# main-unit-psu.net
KiCad netlist of a schematic drawn in EAGLE
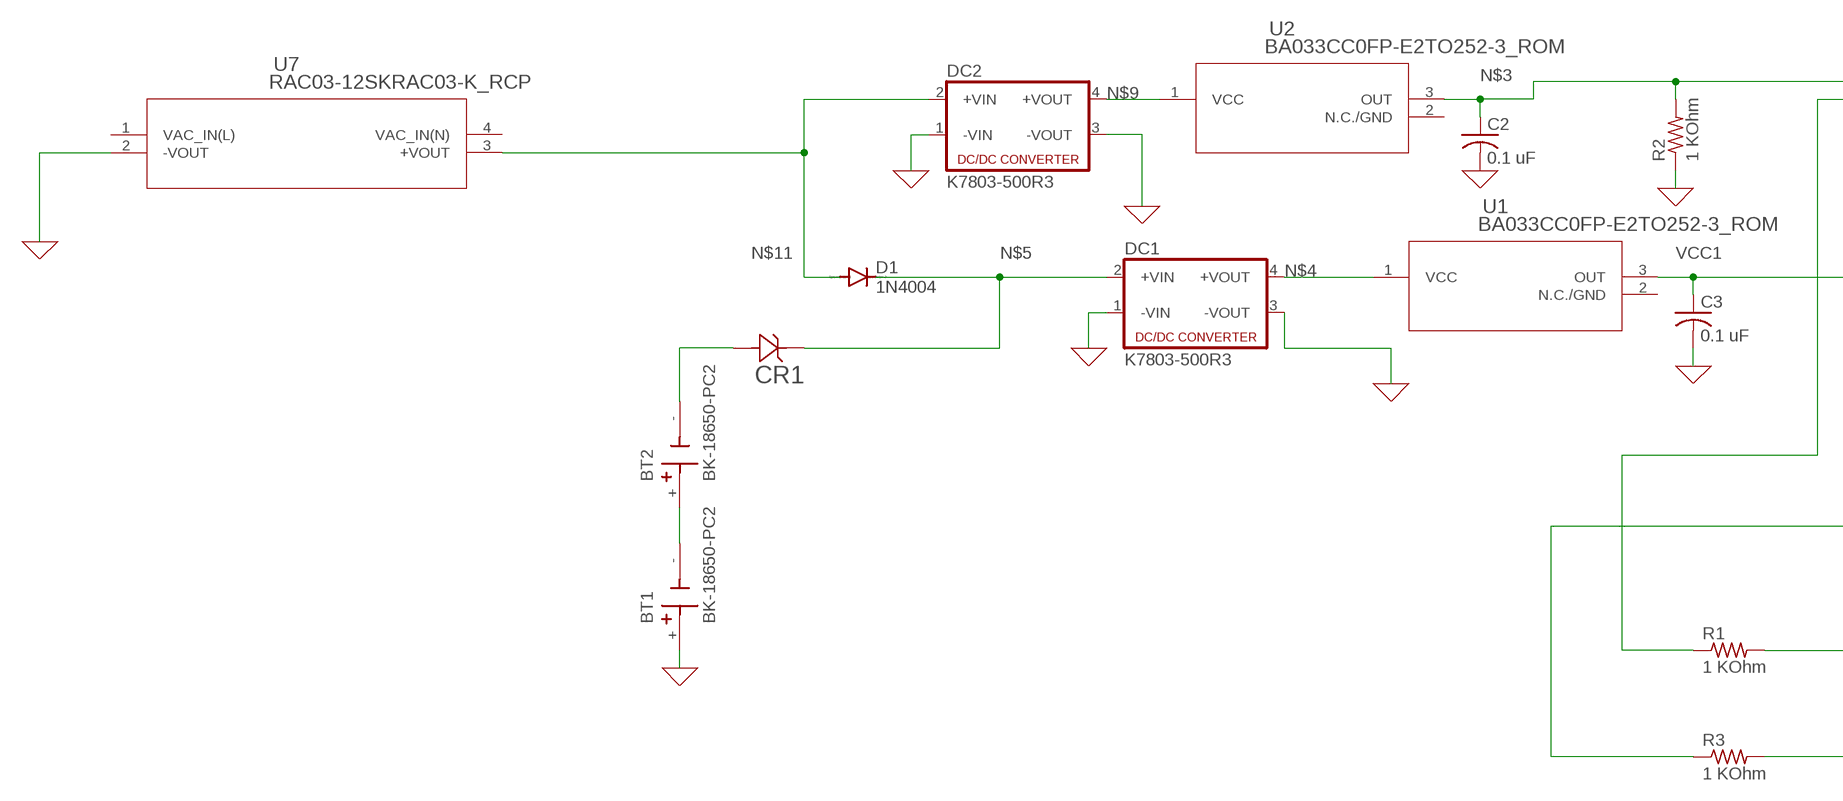
[diagram p0: schematic, sheet 1, part 1 of 2]
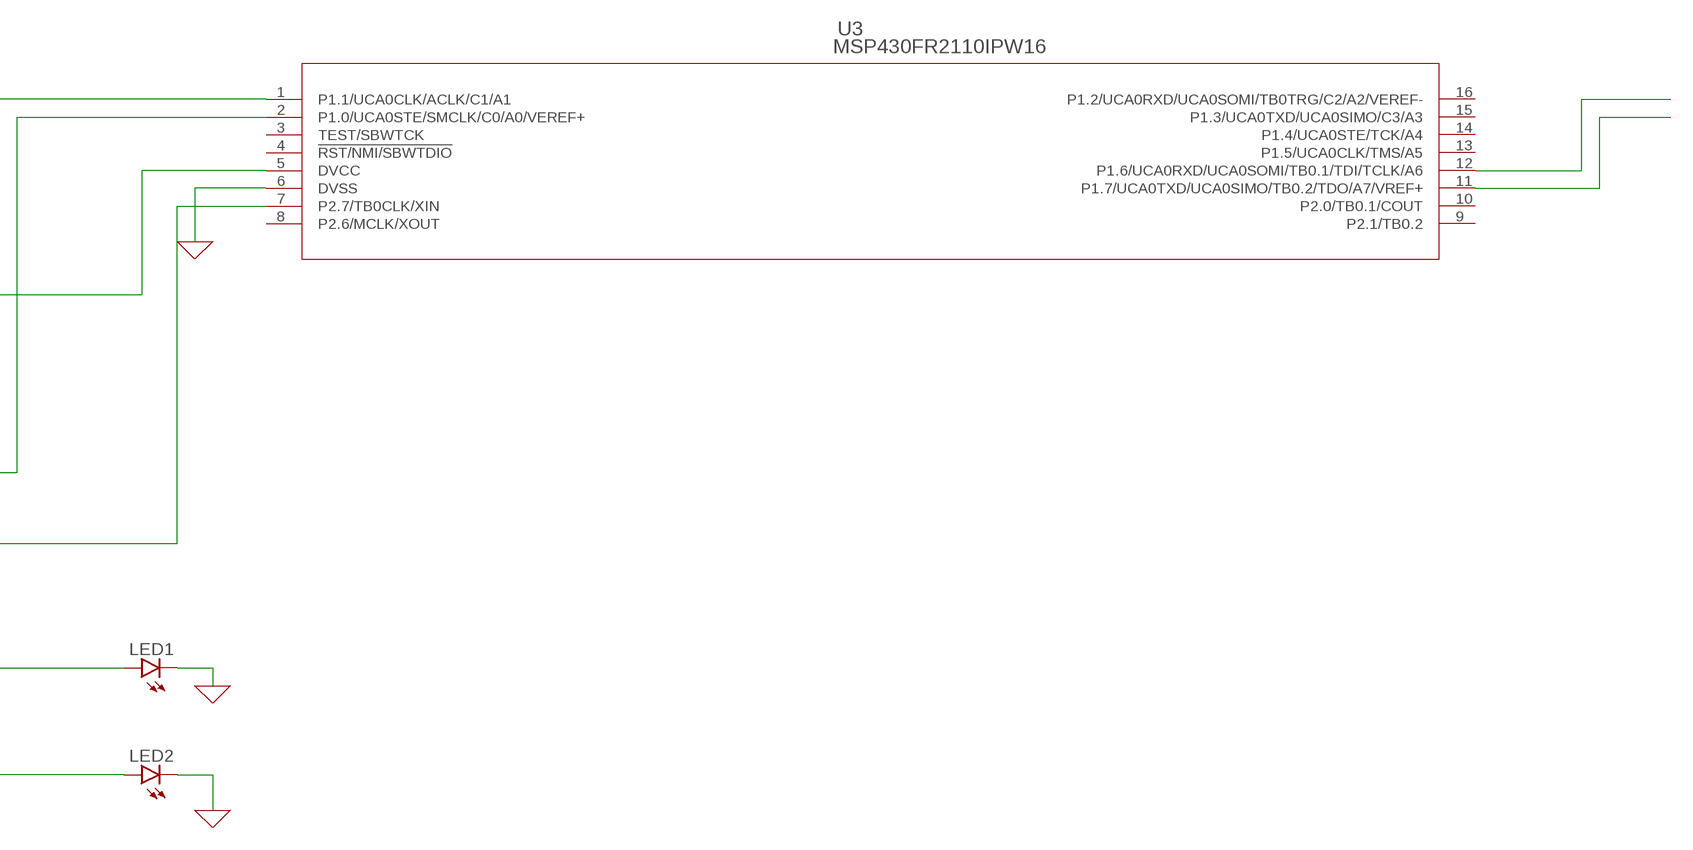
[diagram p1: schematic, sheet 1, part 2 of 2]

(export (version "E")
  (design (tool "Eeschema 10.0.6"))
  (components
    (comp (ref "BT1")
      (value "BK-18650-PC2")
      (footprint "eagle-import:BAT_BK-18650-PC2")
      (fields (field (name "MF") "MPD (Memory Protection Devices)"))
      (libsource (lib "eagle-import") (part "BK-18650-PC2"))
    )
    (comp (ref "BT2")
      (value "BK-18650-PC2")
      (footprint "eagle-import:BAT_BK-18650-PC2")
      (fields (field (name "MF") "MPD (Memory Protection Devices)"))
      (libsource (lib "eagle-import") (part "BK-18650-PC2"))
    )
    (comp (ref "C2")
      (value "0.1 uF")
      (footprint "eagle-import:C050-024X044")
      (libsource (lib "eagle-import") (part "C-US050-024X044"))
    )
    (comp (ref "C3")
      (value "0.1 uF")
      (footprint "eagle-import:C050-024X044")
      (libsource (lib "eagle-import") (part "C-US050-024X044"))
    )
    (comp (ref "CR1")
      (value "1N5819DO-41_STM")
      (footprint "eagle-import:DO-41_STM")
      (fields
        (field (name "MANUFACTURER_PART_NUMBER") "1N5819")
        (field (name "COPYRIGHT") "Copyright (C) 2023 Ultra Librarian. All rights reserved.")
      )
      (libsource (lib "eagle-import") (part "1N5819DO-41_STM"))
    )
    (comp (ref "D1")
      (value "1N4004")
      (footprint "eagle-import:DO41-10")
      (libsource (lib "eagle-import") (part "1N4004"))
    )
    (comp (ref "DC1")
      (value "K7803-500R3")
      (footprint "eagle-import:NME")
      (fields (field (name "MF") "C & D TECHNOLOGIES, INC") (field (name "MPN") "NME1205D"))
      (libsource (lib "eagle-import") (part "NME"))
    )
    (comp (ref "DC2")
      (value "K7803-500R3")
      (footprint "eagle-import:NME")
      (fields (field (name "MF") "C & D TECHNOLOGIES, INC") (field (name "MPN") "NME1205D"))
      (libsource (lib "eagle-import") (part "NME"))
    )
    (comp (ref "LED1")
      (value "LED5MM")
      (footprint "eagle-import:LED5MM")
      (libsource (lib "eagle-import") (part "LED5MM"))
    )
    (comp (ref "LED2")
      (value "LED5MM")
      (footprint "eagle-import:LED5MM")
      (libsource (lib "eagle-import") (part "LED5MM"))
    )
    (comp (ref "R1")
      (value "1 KOhm")
      (footprint "eagle-import:0204_7")
      (libsource (lib "eagle-import") (part "R-US_0204/7"))
    )
    (comp (ref "R2")
      (value "1 KOhm")
      (footprint "eagle-import:0207_2V")
      (libsource (lib "eagle-import") (part "R-US_0207/2V"))
    )
    (comp (ref "R3")
      (value "1 KOhm")
      (footprint "eagle-import:0204_7")
      (libsource (lib "eagle-import") (part "R-US_0204/7"))
    )
    (comp (ref "U1")
      (value "BA033CC0FP-E2TO252-3_ROM")
      (footprint "eagle-import:TO252-3_ROM")
      (fields
        (field (name "MANUFACTURER_PART_NUMBER") "BA033CC0FP-E2")
        (field (name "COPYRIGHT") "Copyright (C) 2023 Ultra Librarian. All rights reserved.")
      )
      (libsource (lib "eagle-import") (part "BA033CC0FP-E2TO252-3_ROM"))
    )
    (comp (ref "U2")
      (value "BA033CC0FP-E2TO252-3_ROM")
      (footprint "eagle-import:TO252-3_ROM")
      (fields
        (field (name "MANUFACTURER_PART_NUMBER") "BA033CC0FP-E2")
        (field (name "COPYRIGHT") "Copyright (C) 2023 Ultra Librarian. All rights reserved.")
      )
      (libsource (lib "eagle-import") (part "BA033CC0FP-E2TO252-3_ROM"))
    )
    (comp (ref "U3")
      (value "MSP430FR2110IPW16")
      (footprint "eagle-import:PW16_TEX")
      (fields (field (name "COPYRIGHT") "Copyright (C) 2023 Ultra Librarian. All rights reserved."))
      (libsource (lib "eagle-import") (part "MSP430FR2110IPW16"))
    )
    (comp (ref "U7")
      (value "RAC03-12SKRAC03-K_RCP")
      (footprint "eagle-import:RAC03-K_RCP")
      (fields
        (field (name "MANUFACTURER_PART_NUMBER") "RAC03-12SK")
        (field (name "COPYRIGHT") "Copyright (C) 2023 Ultra Librarian. All rights reserved.")
      )
      (libsource (lib "eagle-import") (part "RAC03-12SKRAC03-K_RCP"))
    )
  )
  (nets
    (net (code "1") (name "/N$3") (class "Default")
      (node (ref "C2") (pin "1") (pinfunction "1_1") (pintype "passive"))
      (node (ref "R2") (pin "2") (pinfunction "2_2") (pintype "passive"))
      (node (ref "U2") (pin "3") (pinfunction "OUT_3") (pintype "output"))
      (node (ref "U3") (pin "1") (pinfunction "P1.1/UCA0CLK/ACLK/C1/A1_1") (pintype "bidirectional"))
    )
    (net (code "2") (name "/N$4") (class "Default")
      (node (ref "DC1") (pin "4") (pinfunction "+VOUT_4") (pintype "passive"))
      (node (ref "U1") (pin "1") (pinfunction "VCC_1") (pintype "power_in"))
    )
    (net (code "3") (name "/N$5") (class "Default")
      (node (ref "CR1") (pin "1") (pinfunction "1_1") (pintype "passive"))
      (node (ref "D1") (pin "C") (pinfunction "C_C") (pintype "passive"))
      (node (ref "DC1") (pin "2") (pinfunction "+VIN_2") (pintype "passive"))
    )
    (net (code "4") (name "/N$9") (class "Default")
      (node (ref "DC2") (pin "4") (pinfunction "+VOUT_4") (pintype "passive"))
      (node (ref "U2") (pin "1") (pinfunction "VCC_1") (pintype "power_in"))
    )
    (net (code "5") (name "/N$11") (class "Default")
      (node (ref "D1") (pin "A") (pinfunction "A_A") (pintype "passive"))
      (node (ref "DC2") (pin "2") (pinfunction "+VIN_2") (pintype "passive"))
      (node (ref "U7") (pin "3") (pinfunction "+VOUT_3") (pintype "output"))
    )
    (net (code "6") (name "/VAC_IN(L)") (class "Default")
      (node (ref "U7") (pin "1") (pinfunction "VAC_IN(L)_1") (pintype "power_in"))
    )
    (net (code "7") (name "/VAC_IN(N)") (class "Default")
      (node (ref "U7") (pin "4") (pinfunction "VAC_IN(N)_4") (pintype "power_in"))
    )
    (net (code "8") (name "/VCC1") (class "Default")
      (node (ref "C3") (pin "1") (pinfunction "1_1") (pintype "passive"))
      (node (ref "U1") (pin "3") (pinfunction "OUT_3") (pintype "output"))
      (node (ref "U3") (pin "5") (pinfunction "DVCC_5") (pintype "power_in"))
    )
    (net (code "9") (name "GND") (class "Default")
      (node (ref "BT1") (pin "+") (pinfunction "+_+") (pintype "passive"))
      (node (ref "C2") (pin "2") (pinfunction "2_2") (pintype "passive"))
      (node (ref "C3") (pin "2") (pinfunction "2_2") (pintype "passive"))
      (node (ref "DC1") (pin "1") (pinfunction "-VIN_1") (pintype "passive"))
      (node (ref "DC1") (pin "3") (pinfunction "-VOUT_3") (pintype "passive"))
      (node (ref "DC2") (pin "1") (pinfunction "-VIN_1") (pintype "passive"))
      (node (ref "DC2") (pin "3") (pinfunction "-VOUT_3") (pintype "passive"))
      (node (ref "LED1") (pin "K") (pinfunction "C_K") (pintype "passive"))
      (node (ref "LED2") (pin "K") (pinfunction "C_K") (pintype "passive"))
      (node (ref "R2") (pin "1") (pinfunction "1_1") (pintype "passive"))
      (node (ref "U3") (pin "6") (pinfunction "DVSS_6") (pintype "passive"))
      (node (ref "U7") (pin "2") (pinfunction "-VOUT_2") (pintype "output"))
    )
    (net (code "10") (name "Net-(BT1-Pad-)") (class "Default")
      (node (ref "BT1") (pin "-") (pinfunction "-_-") (pintype "passive"))
      (node (ref "BT2") (pin "+") (pinfunction "+_+") (pintype "passive"))
    )
    (net (code "11") (name "Net-(BT2-Pad-)") (class "Default")
      (node (ref "BT2") (pin "-") (pinfunction "-_-") (pintype "passive"))
      (node (ref "CR1") (pin "2") (pinfunction "2_2") (pintype "passive"))
    )
    (net (code "12") (name "Net-(LED1-PadA)") (class "Default")
      (node (ref "LED1") (pin "A") (pinfunction "A_A") (pintype "passive"))
      (node (ref "R1") (pin "2") (pinfunction "2_2") (pintype "passive"))
    )
    (net (code "13") (name "Net-(LED2-PadA)") (class "Default")
      (node (ref "LED2") (pin "A") (pinfunction "A_A") (pintype "passive"))
      (node (ref "R3") (pin "2") (pinfunction "2_2") (pintype "passive"))
    )
    (net (code "14") (name "Net-(U3-P1.0{slash}UCA0STE{slash}SMCLK{slash}C0{slash}A0{slash}VEREF+)") (class "Default")
      (node (ref "R1") (pin "1") (pinfunction "1_1") (pintype "passive"))
      (node (ref "U3") (pin "2") (pinfunction "P1.0/UCA0STE/SMCLK/C0/A0/VEREF+_2") (pintype "bidirectional"))
    )
    (net (code "15") (name "Net-(U3-P2.7{slash}TB0CLK{slash}XIN)") (class "Default")
      (node (ref "R3") (pin "1") (pinfunction "1_1") (pintype "passive"))
      (node (ref "U3") (pin "7") (pinfunction "P2.7/TB0CLK/XIN_7") (pintype "bidirectional"))
    )
    (net (code "16") (name "unconnected-(U1-N.C.{slash}GND-Pad2)") (class "Default")
      (node (ref "U1") (pin "2") (pinfunction "N.C./GND_2") (pintype "no_connect"))
    )
    (net (code "17") (name "unconnected-(U2-N.C.{slash}GND-Pad2)") (class "Default")
      (node (ref "U2") (pin "2") (pinfunction "N.C./GND_2") (pintype "no_connect"))
    )
    (net (code "18") (name "unconnected-(U3-P1.2{slash}UCA0RXD{slash}UCA0SOMI{slash}TB0TRG{slash}C2{slash}A2{slash}VEREF--Pad16)") (class "Default")
      (node (ref "U3") (pin "16") (pinfunction "P1.2/UCA0RXD/UCA0SOMI/TB0TRG/C2/A2/VEREF-_16") (pintype "bidirectional"))
    )
    (net (code "19") (name "unconnected-(U3-P1.3{slash}UCA0TXD{slash}UCA0SIMO{slash}C3{slash}A3-Pad15)") (class "Default")
      (node (ref "U3") (pin "15") (pinfunction "P1.3/UCA0TXD/UCA0SIMO/C3/A3_15") (pintype "bidirectional"))
    )
    (net (code "20") (name "unconnected-(U3-P1.4{slash}UCA0STE{slash}TCK{slash}A4-Pad14)") (class "Default")
      (node (ref "U3") (pin "14") (pinfunction "P1.4/UCA0STE/TCK/A4_14") (pintype "bidirectional"))
    )
    (net (code "21") (name "unconnected-(U3-P1.5{slash}UCA0CLK{slash}TMS{slash}A5-Pad13)") (class "Default")
      (node (ref "U3") (pin "13") (pinfunction "P1.5/UCA0CLK/TMS/A5_13") (pintype "bidirectional"))
    )
    (net (code "22") (name "unconnected-(U3-P1.6{slash}UCA0RXD{slash}UCA0SOMI{slash}TB0.1{slash}TDI{slash}TCLK{slash}A6-Pad12)") (class "Default")
      (node (ref "U3") (pin "12") (pinfunction "P1.6/UCA0RXD/UCA0SOMI/TB0.1/TDI/TCLK/A6_12") (pintype "bidirectional"))
    )
    (net (code "23") (name "unconnected-(U3-P1.7{slash}UCA0TXD{slash}UCA0SIMO{slash}TB0.2{slash}TDO{slash}A7{slash}VREF+-Pad11)") (class "Default")
      (node (ref "U3") (pin "11") (pinfunction "P1.7/UCA0TXD/UCA0SIMO/TB0.2/TDO/A7/VREF+_11") (pintype "bidirectional"))
    )
    (net (code "24") (name "unconnected-(U3-P2.0{slash}TB0.1{slash}COUT-Pad10)") (class "Default")
      (node (ref "U3") (pin "10") (pinfunction "P2.0/TB0.1/COUT_10") (pintype "bidirectional"))
    )
    (net (code "25") (name "unconnected-(U3-P2.1{slash}TB0.2-Pad9)") (class "Default")
      (node (ref "U3") (pin "9") (pinfunction "P2.1/TB0.2_9") (pintype "bidirectional"))
    )
    (net (code "26") (name "unconnected-(U3-P2.6{slash}MCLK{slash}XOUT-Pad8)") (class "Default")
      (node (ref "U3") (pin "8") (pinfunction "P2.6/MCLK/XOUT_8") (pintype "bidirectional"))
    )
    (net (code "27") (name "unconnected-(U3-TEST{slash}SBWTCK-Pad3)") (class "Default")
      (node (ref "U3") (pin "3") (pinfunction "TEST/SBWTCK_3") (pintype "input"))
    )
    (net (code "28") (name "unconnected-(U3-~{RST{slash}NMI{slash}SBWTDIO}-Pad4)") (class "Default")
      (node (ref "U3") (pin "4") (pinfunction "~{RST/NMI/SBWTDIO}_4") (pintype "bidirectional"))
    )
  )
)
